# Microscope_Lamp.net
KiCad netlist of a schematic drawn in Altium Designer
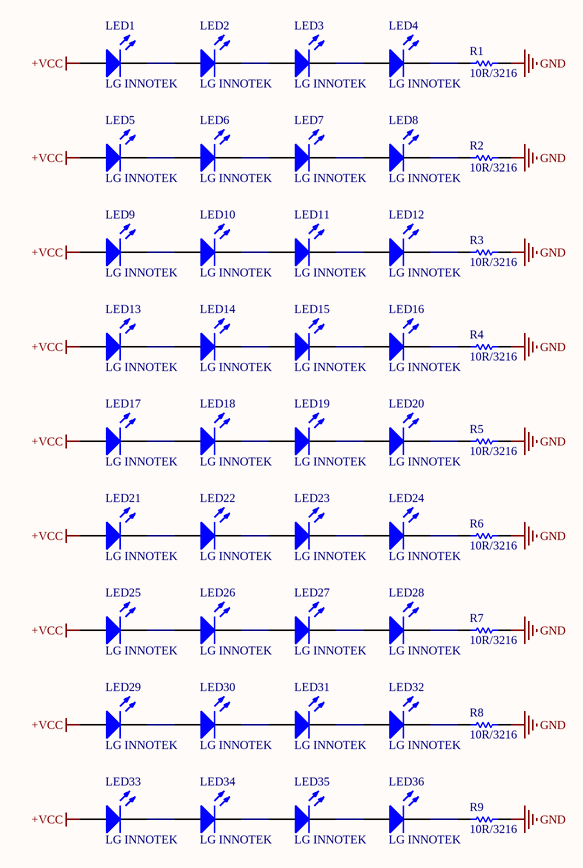
[diagram p0: Microscope_Lamp.SchDoc]

(export (version "E")
  (design (tool "Eeschema 10.0.6"))
  (components
    (comp (ref "LED1")
      (value "LG INNOTEK")
      (footprint "LED_5630")
      (description "Typical RED GaAs LED")
      (libsource (lib "Miscellaneous Devices") (part "LED1"))
    )
    (comp (ref "LED2")
      (value "LG INNOTEK")
      (footprint "LED_5630")
      (description "Typical RED GaAs LED")
      (libsource (lib "Miscellaneous Devices") (part "LED1"))
    )
    (comp (ref "LED3")
      (value "LG INNOTEK")
      (footprint "LED_5630")
      (description "Typical RED GaAs LED")
      (libsource (lib "Miscellaneous Devices") (part "LED1"))
    )
    (comp (ref "LED4")
      (value "LG INNOTEK")
      (footprint "LED_5630")
      (description "Typical RED GaAs LED")
      (libsource (lib "Miscellaneous Devices") (part "LED1"))
    )
    (comp (ref "LED5")
      (value "LG INNOTEK")
      (footprint "LED_5630")
      (description "Typical RED GaAs LED")
      (libsource (lib "Miscellaneous Devices") (part "LED1"))
    )
    (comp (ref "LED6")
      (value "LG INNOTEK")
      (footprint "LED_5630")
      (description "Typical RED GaAs LED")
      (libsource (lib "Miscellaneous Devices") (part "LED1"))
    )
    (comp (ref "LED7")
      (value "LG INNOTEK")
      (footprint "LED_5630")
      (description "Typical RED GaAs LED")
      (libsource (lib "Miscellaneous Devices") (part "LED1"))
    )
    (comp (ref "LED8")
      (value "LG INNOTEK")
      (footprint "LED_5630")
      (description "Typical RED GaAs LED")
      (libsource (lib "Miscellaneous Devices") (part "LED1"))
    )
    (comp (ref "LED9")
      (value "LG INNOTEK")
      (footprint "LED_5630")
      (description "Typical RED GaAs LED")
      (libsource (lib "Miscellaneous Devices") (part "LED1"))
    )
    (comp (ref "LED10")
      (value "LG INNOTEK")
      (footprint "LED_5630")
      (description "Typical RED GaAs LED")
      (libsource (lib "Miscellaneous Devices") (part "LED1"))
    )
    (comp (ref "LED11")
      (value "LG INNOTEK")
      (footprint "LED_5630")
      (description "Typical RED GaAs LED")
      (libsource (lib "Miscellaneous Devices") (part "LED1"))
    )
    (comp (ref "LED12")
      (value "LG INNOTEK")
      (footprint "LED_5630")
      (description "Typical RED GaAs LED")
      (libsource (lib "Miscellaneous Devices") (part "LED1"))
    )
    (comp (ref "LED13")
      (value "LG INNOTEK")
      (footprint "LED_5630")
      (description "Typical RED GaAs LED")
      (libsource (lib "Miscellaneous Devices") (part "LED1"))
    )
    (comp (ref "LED14")
      (value "LG INNOTEK")
      (footprint "LED_5630")
      (description "Typical RED GaAs LED")
      (libsource (lib "Miscellaneous Devices") (part "LED1"))
    )
    (comp (ref "LED15")
      (value "LG INNOTEK")
      (footprint "LED_5630")
      (description "Typical RED GaAs LED")
      (libsource (lib "Miscellaneous Devices") (part "LED1"))
    )
    (comp (ref "LED16")
      (value "LG INNOTEK")
      (footprint "LED_5630")
      (description "Typical RED GaAs LED")
      (libsource (lib "Miscellaneous Devices") (part "LED1"))
    )
    (comp (ref "LED17")
      (value "LG INNOTEK")
      (footprint "LED_5630")
      (description "Typical RED GaAs LED")
      (libsource (lib "Miscellaneous Devices") (part "LED1"))
    )
    (comp (ref "LED18")
      (value "LG INNOTEK")
      (footprint "LED_5630")
      (description "Typical RED GaAs LED")
      (libsource (lib "Miscellaneous Devices") (part "LED1"))
    )
    (comp (ref "LED19")
      (value "LG INNOTEK")
      (footprint "LED_5630")
      (description "Typical RED GaAs LED")
      (libsource (lib "Miscellaneous Devices") (part "LED1"))
    )
    (comp (ref "LED20")
      (value "LG INNOTEK")
      (footprint "LED_5630")
      (description "Typical RED GaAs LED")
      (libsource (lib "Miscellaneous Devices") (part "LED1"))
    )
    (comp (ref "LED21")
      (value "LG INNOTEK")
      (footprint "LED_5630")
      (description "Typical RED GaAs LED")
      (libsource (lib "Miscellaneous Devices") (part "LED1"))
    )
    (comp (ref "LED22")
      (value "LG INNOTEK")
      (footprint "LED_5630")
      (description "Typical RED GaAs LED")
      (libsource (lib "Miscellaneous Devices") (part "LED1"))
    )
    (comp (ref "LED23")
      (value "LG INNOTEK")
      (footprint "LED_5630")
      (description "Typical RED GaAs LED")
      (libsource (lib "Miscellaneous Devices") (part "LED1"))
    )
    (comp (ref "LED24")
      (value "LG INNOTEK")
      (footprint "LED_5630")
      (description "Typical RED GaAs LED")
      (libsource (lib "Miscellaneous Devices") (part "LED1"))
    )
    (comp (ref "LED25")
      (value "LG INNOTEK")
      (footprint "LED_5630")
      (description "Typical RED GaAs LED")
      (libsource (lib "Miscellaneous Devices") (part "LED1"))
    )
    (comp (ref "LED26")
      (value "LG INNOTEK")
      (footprint "LED_5630")
      (description "Typical RED GaAs LED")
      (libsource (lib "Miscellaneous Devices") (part "LED1"))
    )
    (comp (ref "LED27")
      (value "LG INNOTEK")
      (footprint "LED_5630")
      (description "Typical RED GaAs LED")
      (libsource (lib "Miscellaneous Devices") (part "LED1"))
    )
    (comp (ref "LED28")
      (value "LG INNOTEK")
      (footprint "LED_5630")
      (description "Typical RED GaAs LED")
      (libsource (lib "Miscellaneous Devices") (part "LED1"))
    )
    (comp (ref "LED29")
      (value "LG INNOTEK")
      (footprint "LED_5630")
      (description "Typical RED GaAs LED")
      (libsource (lib "Miscellaneous Devices") (part "LED1"))
    )
    (comp (ref "LED30")
      (value "LG INNOTEK")
      (footprint "LED_5630")
      (description "Typical RED GaAs LED")
      (libsource (lib "Miscellaneous Devices") (part "LED1"))
    )
    (comp (ref "LED31")
      (value "LG INNOTEK")
      (footprint "LED_5630")
      (description "Typical RED GaAs LED")
      (libsource (lib "Miscellaneous Devices") (part "LED1"))
    )
    (comp (ref "LED32")
      (value "LG INNOTEK")
      (footprint "LED_5630")
      (description "Typical RED GaAs LED")
      (libsource (lib "Miscellaneous Devices") (part "LED1"))
    )
    (comp (ref "LED33")
      (value "LG INNOTEK")
      (footprint "LED_5630")
      (description "Typical RED GaAs LED")
      (libsource (lib "Miscellaneous Devices") (part "LED1"))
    )
    (comp (ref "LED34")
      (value "LG INNOTEK")
      (footprint "LED_5630")
      (description "Typical RED GaAs LED")
      (libsource (lib "Miscellaneous Devices") (part "LED1"))
    )
    (comp (ref "LED35")
      (value "LG INNOTEK")
      (footprint "LED_5630")
      (description "Typical RED GaAs LED")
      (libsource (lib "Miscellaneous Devices") (part "LED1"))
    )
    (comp (ref "LED36")
      (value "LG INNOTEK")
      (footprint "LED_5630")
      (description "Typical RED GaAs LED")
      (libsource (lib "Miscellaneous Devices") (part "LED1"))
    )
    (comp (ref "R1")
      (value "10R/3216")
      (footprint "RES3216X07N")
      (description "Resistor")
      (libsource (lib "Miscellaneous Devices") (part "Res1"))
    )
    (comp (ref "R2")
      (value "10R/3216")
      (footprint "RES3216X07N")
      (description "Resistor")
      (libsource (lib "Miscellaneous Devices") (part "Res1"))
    )
    (comp (ref "R3")
      (value "10R/3216")
      (footprint "RES3216X07N")
      (description "Resistor")
      (libsource (lib "Miscellaneous Devices") (part "Res1"))
    )
    (comp (ref "R4")
      (value "10R/3216")
      (footprint "RES3216X07N")
      (description "Resistor")
      (libsource (lib "Miscellaneous Devices") (part "Res1"))
    )
    (comp (ref "R5")
      (value "10R/3216")
      (footprint "RES3216X07N")
      (description "Resistor")
      (libsource (lib "Miscellaneous Devices") (part "Res1"))
    )
    (comp (ref "R6")
      (value "10R/3216")
      (footprint "RES3216X07N")
      (description "Resistor")
      (libsource (lib "Miscellaneous Devices") (part "Res1"))
    )
    (comp (ref "R7")
      (value "10R/3216")
      (footprint "RES3216X07N")
      (description "Resistor")
      (libsource (lib "Miscellaneous Devices") (part "Res1"))
    )
    (comp (ref "R8")
      (value "10R/3216")
      (footprint "RES3216X07N")
      (description "Resistor")
      (libsource (lib "Miscellaneous Devices") (part "Res1"))
    )
    (comp (ref "R9")
      (value "10R/3216")
      (footprint "RES3216X07N")
      (description "Resistor")
      (libsource (lib "Miscellaneous Devices") (part "Res1"))
    )
  )
  (nets
    (net (code "1") (name "+VCC") (class "Default")
      (node (ref "LED1") (pin "1") (pinfunction "A_1") (pintype "passive"))
      (node (ref "LED13") (pin "1") (pinfunction "A_1") (pintype "passive"))
      (node (ref "LED17") (pin "1") (pinfunction "A_1") (pintype "passive"))
      (node (ref "LED21") (pin "1") (pinfunction "A_1") (pintype "passive"))
      (node (ref "LED25") (pin "1") (pinfunction "A_1") (pintype "passive"))
      (node (ref "LED29") (pin "1") (pinfunction "A_1") (pintype "passive"))
      (node (ref "LED33") (pin "1") (pinfunction "A_1") (pintype "passive"))
      (node (ref "LED5") (pin "1") (pinfunction "A_1") (pintype "passive"))
      (node (ref "LED9") (pin "1") (pinfunction "A_1") (pintype "passive"))
    )
    (net (code "2") (name "GND") (class "Default")
      (node (ref "R1") (pin "2") (pinfunction "2_2") (pintype "passive"))
      (node (ref "R2") (pin "2") (pinfunction "2_2") (pintype "passive"))
      (node (ref "R3") (pin "2") (pinfunction "2_2") (pintype "passive"))
      (node (ref "R4") (pin "2") (pinfunction "2_2") (pintype "passive"))
      (node (ref "R5") (pin "2") (pinfunction "2_2") (pintype "passive"))
      (node (ref "R6") (pin "2") (pinfunction "2_2") (pintype "passive"))
      (node (ref "R7") (pin "2") (pinfunction "2_2") (pintype "passive"))
      (node (ref "R8") (pin "2") (pinfunction "2_2") (pintype "passive"))
      (node (ref "R9") (pin "2") (pinfunction "2_2") (pintype "passive"))
    )
    (net (code "3") (name "Net-(LED1-K)") (class "Default")
      (node (ref "LED1") (pin "2") (pinfunction "K_2") (pintype "passive"))
      (node (ref "LED2") (pin "1") (pinfunction "A_1") (pintype "passive"))
    )
    (net (code "4") (name "Net-(LED2-K)") (class "Default")
      (node (ref "LED2") (pin "2") (pinfunction "K_2") (pintype "passive"))
      (node (ref "LED3") (pin "1") (pinfunction "A_1") (pintype "passive"))
    )
    (net (code "5") (name "Net-(LED3-K)") (class "Default")
      (node (ref "LED3") (pin "2") (pinfunction "K_2") (pintype "passive"))
      (node (ref "LED4") (pin "1") (pinfunction "A_1") (pintype "passive"))
    )
    (net (code "6") (name "Net-(LED4-K)") (class "Default")
      (node (ref "LED4") (pin "2") (pinfunction "K_2") (pintype "passive"))
      (node (ref "R1") (pin "1") (pinfunction "1_1") (pintype "passive"))
    )
    (net (code "7") (name "Net-(LED5-K)") (class "Default")
      (node (ref "LED5") (pin "2") (pinfunction "K_2") (pintype "passive"))
      (node (ref "LED6") (pin "1") (pinfunction "A_1") (pintype "passive"))
    )
    (net (code "8") (name "Net-(LED6-K)") (class "Default")
      (node (ref "LED6") (pin "2") (pinfunction "K_2") (pintype "passive"))
      (node (ref "LED7") (pin "1") (pinfunction "A_1") (pintype "passive"))
    )
    (net (code "9") (name "Net-(LED7-K)") (class "Default")
      (node (ref "LED7") (pin "2") (pinfunction "K_2") (pintype "passive"))
      (node (ref "LED8") (pin "1") (pinfunction "A_1") (pintype "passive"))
    )
    (net (code "10") (name "Net-(LED8-K)") (class "Default")
      (node (ref "LED8") (pin "2") (pinfunction "K_2") (pintype "passive"))
      (node (ref "R2") (pin "1") (pinfunction "1_1") (pintype "passive"))
    )
    (net (code "11") (name "Net-(LED10-A)") (class "Default")
      (node (ref "LED10") (pin "1") (pinfunction "A_1") (pintype "passive"))
      (node (ref "LED9") (pin "2") (pinfunction "K_2") (pintype "passive"))
    )
    (net (code "12") (name "Net-(LED10-K)") (class "Default")
      (node (ref "LED10") (pin "2") (pinfunction "K_2") (pintype "passive"))
      (node (ref "LED11") (pin "1") (pinfunction "A_1") (pintype "passive"))
    )
    (net (code "13") (name "Net-(LED11-K)") (class "Default")
      (node (ref "LED11") (pin "2") (pinfunction "K_2") (pintype "passive"))
      (node (ref "LED12") (pin "1") (pinfunction "A_1") (pintype "passive"))
    )
    (net (code "14") (name "Net-(LED12-K)") (class "Default")
      (node (ref "LED12") (pin "2") (pinfunction "K_2") (pintype "passive"))
      (node (ref "R3") (pin "1") (pinfunction "1_1") (pintype "passive"))
    )
    (net (code "15") (name "Net-(LED13-K)") (class "Default")
      (node (ref "LED13") (pin "2") (pinfunction "K_2") (pintype "passive"))
      (node (ref "LED14") (pin "1") (pinfunction "A_1") (pintype "passive"))
    )
    (net (code "16") (name "Net-(LED14-K)") (class "Default")
      (node (ref "LED14") (pin "2") (pinfunction "K_2") (pintype "passive"))
      (node (ref "LED15") (pin "1") (pinfunction "A_1") (pintype "passive"))
    )
    (net (code "17") (name "Net-(LED15-K)") (class "Default")
      (node (ref "LED15") (pin "2") (pinfunction "K_2") (pintype "passive"))
      (node (ref "LED16") (pin "1") (pinfunction "A_1") (pintype "passive"))
    )
    (net (code "18") (name "Net-(LED16-K)") (class "Default")
      (node (ref "LED16") (pin "2") (pinfunction "K_2") (pintype "passive"))
      (node (ref "R4") (pin "1") (pinfunction "1_1") (pintype "passive"))
    )
    (net (code "19") (name "Net-(LED17-K)") (class "Default")
      (node (ref "LED17") (pin "2") (pinfunction "K_2") (pintype "passive"))
      (node (ref "LED18") (pin "1") (pinfunction "A_1") (pintype "passive"))
    )
    (net (code "20") (name "Net-(LED18-K)") (class "Default")
      (node (ref "LED18") (pin "2") (pinfunction "K_2") (pintype "passive"))
      (node (ref "LED19") (pin "1") (pinfunction "A_1") (pintype "passive"))
    )
    (net (code "21") (name "Net-(LED19-K)") (class "Default")
      (node (ref "LED19") (pin "2") (pinfunction "K_2") (pintype "passive"))
      (node (ref "LED20") (pin "1") (pinfunction "A_1") (pintype "passive"))
    )
    (net (code "22") (name "Net-(LED20-K)") (class "Default")
      (node (ref "LED20") (pin "2") (pinfunction "K_2") (pintype "passive"))
      (node (ref "R5") (pin "1") (pinfunction "1_1") (pintype "passive"))
    )
    (net (code "23") (name "Net-(LED21-K)") (class "Default")
      (node (ref "LED21") (pin "2") (pinfunction "K_2") (pintype "passive"))
      (node (ref "LED22") (pin "1") (pinfunction "A_1") (pintype "passive"))
    )
    (net (code "24") (name "Net-(LED22-K)") (class "Default")
      (node (ref "LED22") (pin "2") (pinfunction "K_2") (pintype "passive"))
      (node (ref "LED23") (pin "1") (pinfunction "A_1") (pintype "passive"))
    )
    (net (code "25") (name "Net-(LED23-K)") (class "Default")
      (node (ref "LED23") (pin "2") (pinfunction "K_2") (pintype "passive"))
      (node (ref "LED24") (pin "1") (pinfunction "A_1") (pintype "passive"))
    )
    (net (code "26") (name "Net-(LED24-K)") (class "Default")
      (node (ref "LED24") (pin "2") (pinfunction "K_2") (pintype "passive"))
      (node (ref "R6") (pin "1") (pinfunction "1_1") (pintype "passive"))
    )
    (net (code "27") (name "Net-(LED25-K)") (class "Default")
      (node (ref "LED25") (pin "2") (pinfunction "K_2") (pintype "passive"))
      (node (ref "LED26") (pin "1") (pinfunction "A_1") (pintype "passive"))
    )
    (net (code "28") (name "Net-(LED26-K)") (class "Default")
      (node (ref "LED26") (pin "2") (pinfunction "K_2") (pintype "passive"))
      (node (ref "LED27") (pin "1") (pinfunction "A_1") (pintype "passive"))
    )
    (net (code "29") (name "Net-(LED27-K)") (class "Default")
      (node (ref "LED27") (pin "2") (pinfunction "K_2") (pintype "passive"))
      (node (ref "LED28") (pin "1") (pinfunction "A_1") (pintype "passive"))
    )
    (net (code "30") (name "Net-(LED28-K)") (class "Default")
      (node (ref "LED28") (pin "2") (pinfunction "K_2") (pintype "passive"))
      (node (ref "R7") (pin "1") (pinfunction "1_1") (pintype "passive"))
    )
    (net (code "31") (name "Net-(LED29-K)") (class "Default")
      (node (ref "LED29") (pin "2") (pinfunction "K_2") (pintype "passive"))
      (node (ref "LED30") (pin "1") (pinfunction "A_1") (pintype "passive"))
    )
    (net (code "32") (name "Net-(LED30-K)") (class "Default")
      (node (ref "LED30") (pin "2") (pinfunction "K_2") (pintype "passive"))
      (node (ref "LED31") (pin "1") (pinfunction "A_1") (pintype "passive"))
    )
    (net (code "33") (name "Net-(LED31-K)") (class "Default")
      (node (ref "LED31") (pin "2") (pinfunction "K_2") (pintype "passive"))
      (node (ref "LED32") (pin "1") (pinfunction "A_1") (pintype "passive"))
    )
    (net (code "34") (name "Net-(LED32-K)") (class "Default")
      (node (ref "LED32") (pin "2") (pinfunction "K_2") (pintype "passive"))
      (node (ref "R8") (pin "1") (pinfunction "1_1") (pintype "passive"))
    )
    (net (code "35") (name "Net-(LED33-K)") (class "Default")
      (node (ref "LED33") (pin "2") (pinfunction "K_2") (pintype "passive"))
      (node (ref "LED34") (pin "1") (pinfunction "A_1") (pintype "passive"))
    )
    (net (code "36") (name "Net-(LED34-K)") (class "Default")
      (node (ref "LED34") (pin "2") (pinfunction "K_2") (pintype "passive"))
      (node (ref "LED35") (pin "1") (pinfunction "A_1") (pintype "passive"))
    )
    (net (code "37") (name "Net-(LED35-K)") (class "Default")
      (node (ref "LED35") (pin "2") (pinfunction "K_2") (pintype "passive"))
      (node (ref "LED36") (pin "1") (pinfunction "A_1") (pintype "passive"))
    )
    (net (code "38") (name "Net-(LED36-K)") (class "Default")
      (node (ref "LED36") (pin "2") (pinfunction "K_2") (pintype "passive"))
      (node (ref "R9") (pin "1") (pinfunction "1_1") (pintype "passive"))
    )
  )
)
